# TX0.net
KiCad netlist of a schematic drawn in Altium Designer
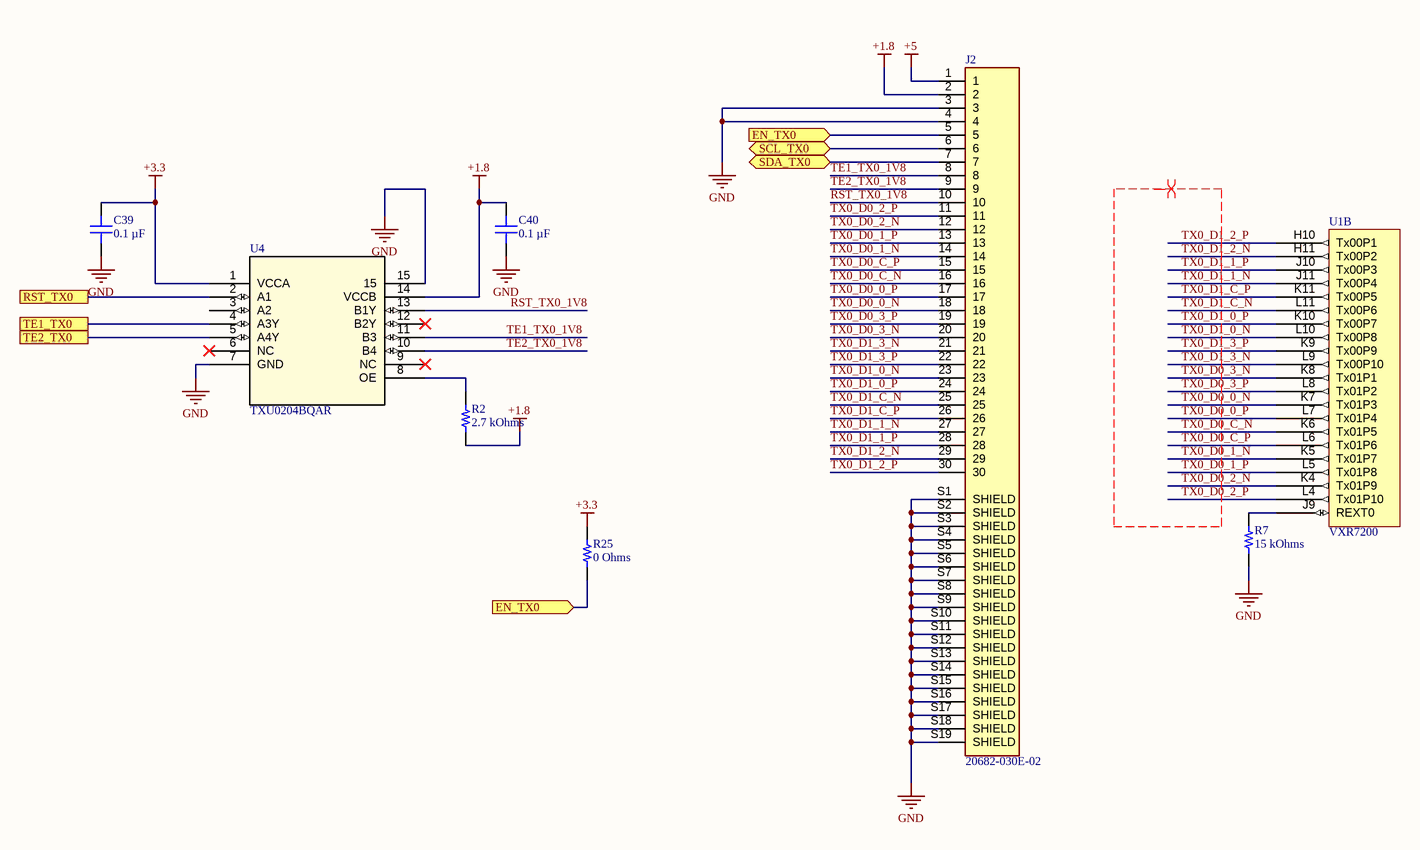
[diagram p0: TX0.SchDoc]

(export (version "E")
  (design (tool "Eeschema 10.0.6"))
  (components
    (comp (ref "C39")
      (value "0.1 µF")
      (footprint "CAP 0201_0603")
      (description "CAP CER 0.1UF 25V X5R 0201")
      (fields
        (field (name "PART NUMBER") "GRM033R61E104KE14D")
        (field (name "MANUFACTURER") "Murata Electronics")
      )
      (libsource (lib "Celestial Altium Library - altium_library") (part "Capacitor"))
    )
    (comp (ref "C40")
      (value "0.1 µF")
      (footprint "CAP 0201_0603")
      (description "CAP CER 0.1UF 25V X5R 0201")
      (fields
        (field (name "PART NUMBER") "GRM033R61E104KE14D")
        (field (name "MANUFACTURER") "Murata Electronics")
      )
      (libsource (lib "Celestial Altium Library - altium_library") (part "Capacitor"))
    )
    (comp (ref "J2")
      (value "20682-030E-02")
      (footprint "20682-030E-02:IPEX_20682-030E-02")
      (description "Cabline-CAII Rece. Ass'y")
      (fields (field (name "MF") "{'manufacturer': u'I-PEX'}"))
      (libsource (lib "*") (part "20682-030E-02"))
    )
    (comp (ref "R2")
      (value "2.7 kOhms")
      (footprint "RES 0201_0603")
      (description "RES 2.7K OHM 5% 1/20W 0201 SMD")
      (fields
        (field (name "PART NUMBER") "ERJ-U01J272C")
        (field (name "MANUFACTURER") "Panasonic Electronic Components")
      )
      (libsource (lib "Celestial Altium Library - altium_library") (part "Resistor"))
    )
    (comp (ref "R7")
      (value "15 kOhms")
      (footprint "RES 0201_0603")
      (description "RES SMD 15K OHM 1% 1/20W 0201")
      (fields
        (field (name "PART NUMBER") "ERJ-1GNF1502C")
        (field (name "MANUFACTURER") "Panasonic Electronic Components")
      )
      (libsource (lib "Celestial Altium Library - altium_library") (part "Resistor"))
    )
    (comp (ref "R25")
      (value "0 Ohms")
      (footprint "RES 0402_1005")
      (description "RESISTOR 0402 JUMPER ZERO OHM")
      (fields (field (name "PART NUMBER") "AC0402FR-070RL") (field (name "MANUFACTURER") "Yageo"))
      (libsource (lib "Celestial Altium Library - altium_library") (part "Resistor"))
    )
    (comp (ref "U1")
      (value "VXR7200")
      (footprint "BGA100P9X9-81A")
      (description "VXR7200 DP to MIPI-DSI bridge")
      (libsource (lib "SimulaVR") (part "VXR7200-Symbol-1"))
    )
    (comp (ref "U4")
      (value "TXU0204BQAR")
      (footprint "WQFN_04BQAR_TEX")
      (description "No Description Available")
      (fields (field (name "COPYRIGHT") "Copyright (C) 2022 Ultra Librarian. All rights reserved."))
      (libsource (lib "SimulaVR") (part "TXU0204BQAR"))
    )
  )
  (nets
    (net (code "1") (name "+1.8") (class "Default")
      (node (ref "C40") (pin "2") (pinfunction "2_2") (pintype "passive"))
      (node (ref "J2") (pin "2") (pinfunction "2_2") (pintype "passive"))
      (node (ref "R2") (pin "1") (pinfunction "1_1") (pintype "passive"))
      (node (ref "U4") (pin "14") (pinfunction "VCCB_14") (pintype "power_in"))
    )
    (net (code "2") (name "+3.3") (class "Default")
      (node (ref "C39") (pin "2") (pinfunction "2_2") (pintype "passive"))
      (node (ref "R25") (pin "2") (pinfunction "2_2") (pintype "passive"))
      (node (ref "U4") (pin "1") (pinfunction "VCCA_1") (pintype "power_in"))
    )
    (net (code "3") (name "+5") (class "Default")
      (node (ref "J2") (pin "1") (pinfunction "1_1") (pintype "passive"))
    )
    (net (code "4") (name "/EN_TX0") (class "Default")
      (node (ref "J2") (pin "5") (pinfunction "5_5") (pintype "passive"))
      (node (ref "R25") (pin "1") (pinfunction "1_1") (pintype "passive"))
    )
    (net (code "5") (name "/RST_TX0") (class "Default")
      (node (ref "U4") (pin "2") (pinfunction "A1_2") (pintype "bidirectional"))
    )
    (net (code "6") (name "/RST_TX0_1V8") (class "Default")
      (node (ref "J2") (pin "10") (pinfunction "10_10") (pintype "passive"))
      (node (ref "U4") (pin "13") (pinfunction "B1Y_13") (pintype "bidirectional"))
    )
    (net (code "7") (name "/SCL_TX0") (class "Default")
      (node (ref "J2") (pin "6") (pinfunction "6_6") (pintype "passive"))
    )
    (net (code "8") (name "/SDA_TX0") (class "Default")
      (node (ref "J2") (pin "7") (pinfunction "7_7") (pintype "passive"))
    )
    (net (code "9") (name "/TE1_TX0") (class "Default")
      (node (ref "U4") (pin "4") (pinfunction "A3Y_4") (pintype "bidirectional"))
    )
    (net (code "10") (name "/TE1_TX0_1V8") (class "Default")
      (node (ref "J2") (pin "8") (pinfunction "8_8") (pintype "passive"))
      (node (ref "U4") (pin "11") (pinfunction "B3_11") (pintype "bidirectional"))
    )
    (net (code "11") (name "/TE2_TX0") (class "Default")
      (node (ref "U4") (pin "5") (pinfunction "A4Y_5") (pintype "bidirectional"))
    )
    (net (code "12") (name "/TE2_TX0_1V8") (class "Default")
      (node (ref "J2") (pin "9") (pinfunction "9_9") (pintype "passive"))
      (node (ref "U4") (pin "10") (pinfunction "B4_10") (pintype "bidirectional"))
    )
    (net (code "13") (name "/TX0_D0_0_N") (class "Default")
      (node (ref "J2") (pin "18") (pinfunction "18_18") (pintype "passive"))
      (node (ref "U1") (pin "K7") (pinfunction "Tx01P3_K7") (pintype "output"))
    )
    (net (code "14") (name "/TX0_D0_0_P") (class "Default")
      (node (ref "J2") (pin "17") (pinfunction "17_17") (pintype "passive"))
      (node (ref "U1") (pin "L7") (pinfunction "Tx01P4_L7") (pintype "output"))
    )
    (net (code "15") (name "/TX0_D0_1_N") (class "Default")
      (node (ref "J2") (pin "14") (pinfunction "14_14") (pintype "passive"))
      (node (ref "U1") (pin "K5") (pinfunction "Tx01P7_K5") (pintype "output"))
    )
    (net (code "16") (name "/TX0_D0_1_P") (class "Default")
      (node (ref "J2") (pin "13") (pinfunction "13_13") (pintype "passive"))
      (node (ref "U1") (pin "L5") (pinfunction "Tx01P8_L5") (pintype "output"))
    )
    (net (code "17") (name "/TX0_D0_2_N") (class "Default")
      (node (ref "J2") (pin "12") (pinfunction "12_12") (pintype "passive"))
      (node (ref "U1") (pin "K4") (pinfunction "Tx01P9_K4") (pintype "output"))
    )
    (net (code "18") (name "/TX0_D0_2_P") (class "Default")
      (node (ref "J2") (pin "11") (pinfunction "11_11") (pintype "passive"))
      (node (ref "U1") (pin "L4") (pinfunction "Tx01P10_L4") (pintype "output"))
    )
    (net (code "19") (name "/TX0_D0_3_N") (class "Default")
      (node (ref "J2") (pin "20") (pinfunction "20_20") (pintype "passive"))
      (node (ref "U1") (pin "K8") (pinfunction "Tx01P1_K8") (pintype "output"))
    )
    (net (code "20") (name "/TX0_D0_3_P") (class "Default")
      (node (ref "J2") (pin "19") (pinfunction "19_19") (pintype "passive"))
      (node (ref "U1") (pin "L8") (pinfunction "Tx01P2_L8") (pintype "output"))
    )
    (net (code "21") (name "/TX0_D0_C_N") (class "Default")
      (node (ref "J2") (pin "16") (pinfunction "16_16") (pintype "passive"))
      (node (ref "U1") (pin "K6") (pinfunction "Tx01P5_K6") (pintype "output"))
    )
    (net (code "22") (name "/TX0_D0_C_P") (class "Default")
      (node (ref "J2") (pin "15") (pinfunction "15_15") (pintype "passive"))
      (node (ref "U1") (pin "L6") (pinfunction "Tx01P6_L6") (pintype "output"))
    )
    (net (code "23") (name "/TX0_D1_0_N") (class "Default")
      (node (ref "J2") (pin "23") (pinfunction "23_23") (pintype "passive"))
      (node (ref "U1") (pin "L10") (pinfunction "Tx00P8_L10") (pintype "output"))
    )
    (net (code "24") (name "/TX0_D1_0_P") (class "Default")
      (node (ref "J2") (pin "24") (pinfunction "24_24") (pintype "passive"))
      (node (ref "U1") (pin "K10") (pinfunction "Tx00P7_K10") (pintype "output"))
    )
    (net (code "25") (name "/TX0_D1_1_N") (class "Default")
      (node (ref "J2") (pin "27") (pinfunction "27_27") (pintype "passive"))
      (node (ref "U1") (pin "J11") (pinfunction "Tx00P4_J11") (pintype "output"))
    )
    (net (code "26") (name "/TX0_D1_1_P") (class "Default")
      (node (ref "J2") (pin "28") (pinfunction "28_28") (pintype "passive"))
      (node (ref "U1") (pin "J10") (pinfunction "Tx00P3_J10") (pintype "output"))
    )
    (net (code "27") (name "/TX0_D1_2_N") (class "Default")
      (node (ref "J2") (pin "29") (pinfunction "29_29") (pintype "passive"))
      (node (ref "U1") (pin "H11") (pinfunction "Tx00P2_H11") (pintype "output"))
    )
    (net (code "28") (name "/TX0_D1_2_P") (class "Default")
      (node (ref "J2") (pin "30") (pinfunction "30_30") (pintype "passive"))
      (node (ref "U1") (pin "H10") (pinfunction "Tx00P1_H10") (pintype "output"))
    )
    (net (code "29") (name "/TX0_D1_3_N") (class "Default")
      (node (ref "J2") (pin "21") (pinfunction "21_21") (pintype "passive"))
      (node (ref "U1") (pin "L9") (pinfunction "Tx00P10_L9") (pintype "output"))
    )
    (net (code "30") (name "/TX0_D1_3_P") (class "Default")
      (node (ref "J2") (pin "22") (pinfunction "22_22") (pintype "passive"))
      (node (ref "U1") (pin "K9") (pinfunction "Tx00P9_K9") (pintype "output"))
    )
    (net (code "31") (name "/TX0_D1_C_N") (class "Default")
      (node (ref "J2") (pin "25") (pinfunction "25_25") (pintype "passive"))
      (node (ref "U1") (pin "L11") (pinfunction "Tx00P6_L11") (pintype "output"))
    )
    (net (code "32") (name "/TX0_D1_C_P") (class "Default")
      (node (ref "J2") (pin "26") (pinfunction "26_26") (pintype "passive"))
      (node (ref "U1") (pin "K11") (pinfunction "Tx00P5_K11") (pintype "output"))
    )
    (net (code "33") (name "GND") (class "Default")
      (node (ref "C39") (pin "1") (pinfunction "1_1") (pintype "passive"))
      (node (ref "C40") (pin "1") (pinfunction "1_1") (pintype "passive"))
      (node (ref "J2") (pin "3") (pinfunction "3_3") (pintype "passive"))
      (node (ref "J2") (pin "4") (pinfunction "4_4") (pintype "passive"))
      (node (ref "J2") (pin "S1") (pinfunction "SHIELD_S1") (pintype "passive"))
      (node (ref "J2") (pin "S10") (pinfunction "SHIELD_S10") (pintype "passive"))
      (node (ref "J2") (pin "S11") (pinfunction "SHIELD_S11") (pintype "passive"))
      (node (ref "J2") (pin "S12") (pinfunction "SHIELD_S12") (pintype "passive"))
      (node (ref "J2") (pin "S13") (pinfunction "SHIELD_S13") (pintype "passive"))
      (node (ref "J2") (pin "S14") (pinfunction "SHIELD_S14") (pintype "passive"))
      (node (ref "J2") (pin "S15") (pinfunction "SHIELD_S15") (pintype "passive"))
      (node (ref "J2") (pin "S16") (pinfunction "SHIELD_S16") (pintype "passive"))
      (node (ref "J2") (pin "S17") (pinfunction "SHIELD_S17") (pintype "passive"))
      (node (ref "J2") (pin "S18") (pinfunction "SHIELD_S18") (pintype "passive"))
      (node (ref "J2") (pin "S19") (pinfunction "SHIELD_S19") (pintype "passive"))
      (node (ref "J2") (pin "S2") (pinfunction "SHIELD_S2") (pintype "passive"))
      (node (ref "J2") (pin "S3") (pinfunction "SHIELD_S3") (pintype "passive"))
      (node (ref "J2") (pin "S4") (pinfunction "SHIELD_S4") (pintype "passive"))
      (node (ref "J2") (pin "S5") (pinfunction "SHIELD_S5") (pintype "passive"))
      (node (ref "J2") (pin "S6") (pinfunction "SHIELD_S6") (pintype "passive"))
      (node (ref "J2") (pin "S7") (pinfunction "SHIELD_S7") (pintype "passive"))
      (node (ref "J2") (pin "S8") (pinfunction "SHIELD_S8") (pintype "passive"))
      (node (ref "J2") (pin "S9") (pinfunction "SHIELD_S9") (pintype "passive"))
      (node (ref "R7") (pin "1") (pinfunction "1_1") (pintype "passive"))
      (node (ref "U4") (pin "15") (pinfunction "15_15") (pintype "passive"))
      (node (ref "U4") (pin "7") (pinfunction "GND_7") (pintype "passive"))
    )
    (net (code "34") (name "Net-(U1B-REXT0)") (class "Default")
      (node (ref "R7") (pin "2") (pinfunction "2_2") (pintype "passive"))
      (node (ref "U1") (pin "J9") (pinfunction "REXT0_J9") (pintype "bidirectional"))
    )
    (net (code "35") (name "Net-(U4-OE)") (class "Default")
      (node (ref "R2") (pin "2") (pinfunction "2_2") (pintype "passive"))
      (node (ref "U4") (pin "8") (pinfunction "OE_8") (pintype "passive"))
    )
    (net (code "36") (name "unconnected-(U4-A2-Pad3)") (class "Default")
      (node (ref "U4") (pin "3") (pinfunction "A2_3") (pintype "bidirectional"))
    )
    (net (code "37") (name "unconnected-(U4-B2Y-Pad12)") (class "Default")
      (node (ref "U4") (pin "12") (pinfunction "B2Y_12") (pintype "bidirectional+no_connect"))
    )
    (net (code "38") (name "unconnected-(U4-NC-Pad6)") (class "Default")
      (node (ref "U4") (pin "6") (pinfunction "NC_6") (pintype "passive+no_connect"))
    )
    (net (code "39") (name "unconnected-(U4-NC-Pad9)") (class "Default")
      (node (ref "U4") (pin "9") (pinfunction "NC_9") (pintype "passive+no_connect"))
    )
  )
)
